# Power.net
KiCad netlist of a schematic drawn in Altium Designer
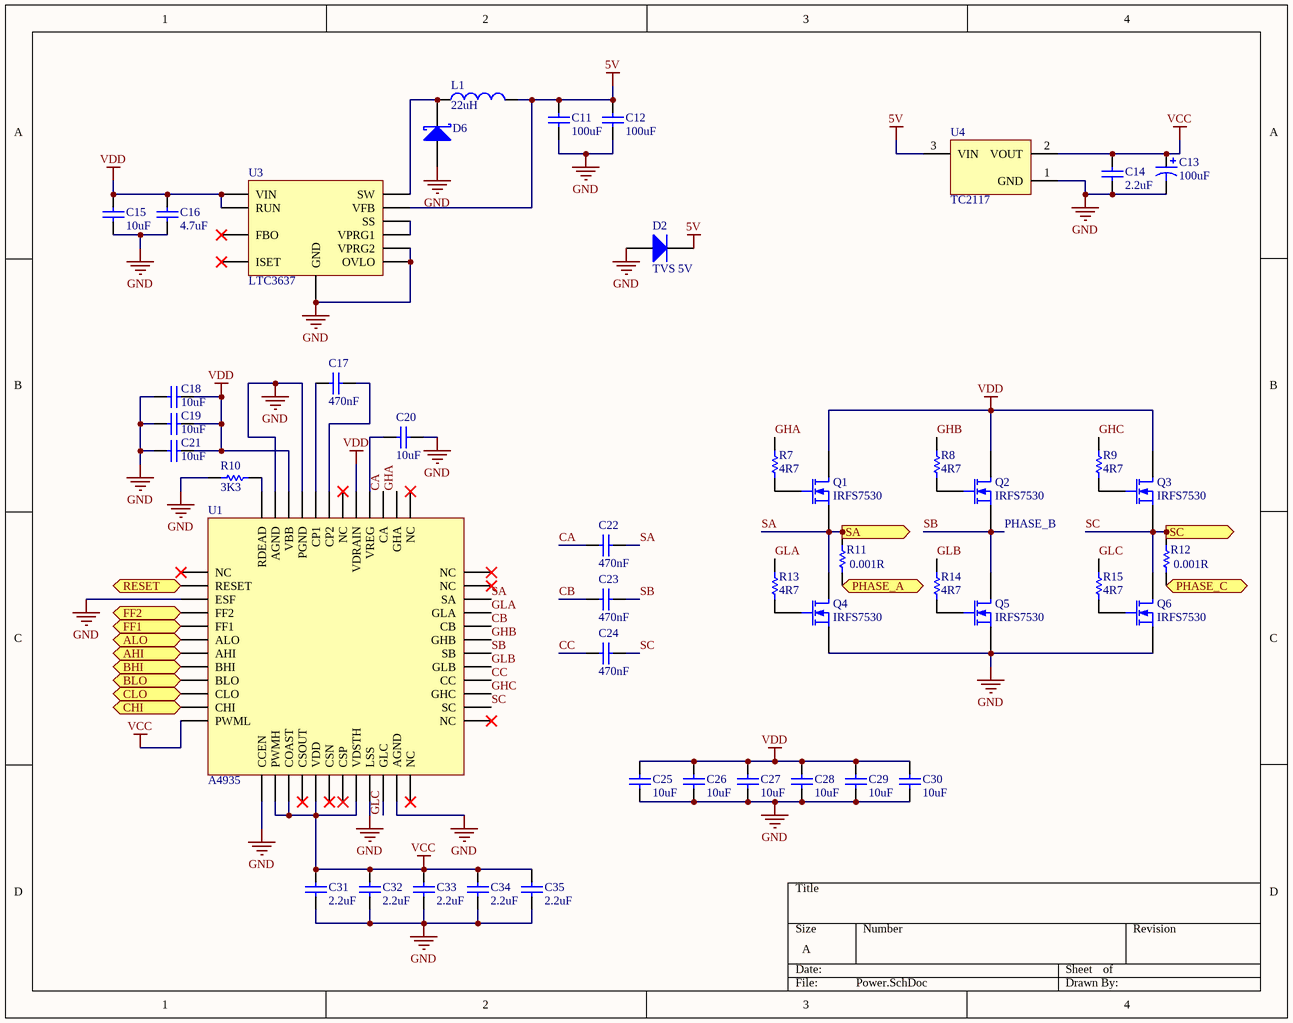
[diagram p0: Power.SchDoc]

(export (version "E")
  (design (tool "Eeschema 10.0.6"))
  (components
    (comp (ref "C11")
      (value "100uF")
      (footprint "CAPC1210(3225)280_N")
      (description "CAP 100uF 10V Â±10% 1210 (3225 Metric) Thickness 2.8mm SMD")
      (fields (field (name "TOLERANCE") "Â±10%"))
      (libsource (lib "Altium Content Vault") (part "CMP-1038-02301-1"))
    )
    (comp (ref "C12")
      (value "100uF")
      (footprint "CAPC1210(3225)280_N")
      (description "CAP 100uF 10V Â±10% 1210 (3225 Metric) Thickness 2.8mm SMD")
      (fields (field (name "TOLERANCE") "Â±10%"))
      (libsource (lib "Altium Content Vault") (part "CMP-1038-02301-1"))
    )
    (comp (ref "C13")
      (value "100uF")
      (footprint "AVX-CAPC7343_V")
      (libsource (lib "Components") (part "AVX-CAP-P-2"))
    )
    (comp (ref "C14")
      (value "2.2uF")
      (footprint "CAPC0603(1608)55_N")
      (description "CAP 2.2uF 16V Â±10% 0603 (1608 Metric) Thickness 0.55mm SMD")
      (fields (field (name "TOLERANCE") "Â±10%"))
      (libsource (lib "Altium Content Vault") (part "CMP-1035-02762-1"))
    )
    (comp (ref "C15")
      (value "10uF")
      (footprint "CAPC1206(3216)190_M")
      (description "CAP 10uF 50V Â±10% 1206 (3216 Metric) Thickness 1.9mm SMD")
      (fields (field (name "TOLERANCE") "Â±10%"))
      (libsource (lib "Altium Content Vault") (part "CAP"))
    )
    (comp (ref "C16")
      (value "4.7uF")
      (footprint "CAPC0805(2012)145_N")
      (description "CAP 4.7uF 50V Â±10% 0805 (2012 Metric) Thickness 1.45mm SMD")
      (fields (field (name "TOLERANCE") "Â±10%"))
      (libsource (lib "Altium Content Vault") (part "CAP"))
    )
    (comp (ref "C17")
      (value "470nF")
      (footprint "CAPC0603(1608)100_N")
      (description "CAP 470nF 25V Â±20% 0603 (1608 Metric) Thickness 1mm SMD")
      (fields (field (name "TOLERANCE") "Â±20%"))
      (libsource (lib "Altium Content Vault") (part "CAP"))
    )
    (comp (ref "C18")
      (value "10uF")
      (footprint "CAPC1206(3216)190_M")
      (description "CAP 10uF 50V Â±10% 1206 (3216 Metric) Thickness 1.9mm SMD")
      (fields (field (name "TOLERANCE") "Â±10%"))
      (libsource (lib "Altium Content Vault") (part "CAP"))
    )
    (comp (ref "C19")
      (value "10uF")
      (footprint "CAPC1206(3216)190_M")
      (description "CAP 10uF 50V Â±10% 1206 (3216 Metric) Thickness 1.9mm SMD")
      (fields (field (name "TOLERANCE") "Â±10%"))
      (libsource (lib "Altium Content Vault") (part "CAP"))
    )
    (comp (ref "C20")
      (value "10uF")
      (footprint "CAPC0805(2012)145_N")
      (description "CAP 10uF 25V Â±10% 0805 (2012 Metric) Thickness 1.45mm SMD")
      (fields (field (name "TOLERANCE") "Â±10%"))
      (libsource (lib "Altium Content Vault") (part "CAP"))
    )
    (comp (ref "C21")
      (value "10uF")
      (footprint "CAPC1206(3216)190_M")
      (description "CAP 10uF 50V Â±10% 1206 (3216 Metric) Thickness 1.9mm SMD")
      (fields (field (name "TOLERANCE") "Â±10%"))
      (libsource (lib "Altium Content Vault") (part "CAP"))
    )
    (comp (ref "C22")
      (value "470nF")
      (footprint "CAPC0603(1608)100_L")
      (description "CAP 470nF 25V Â±10% 0603 (1608 Metric) Thickness 1mm SMD")
      (fields (field (name "TOLERANCE") "Â±10%"))
      (libsource (lib "Altium Content Vault") (part "CAP"))
    )
    (comp (ref "C23")
      (value "470nF")
      (footprint "CAPC0603(1608)100_L")
      (description "CAP 470nF 25V Â±10% 0603 (1608 Metric) Thickness 1mm SMD")
      (fields (field (name "TOLERANCE") "Â±10%"))
      (libsource (lib "Altium Content Vault") (part "CAP"))
    )
    (comp (ref "C24")
      (value "470nF")
      (footprint "CAPC0603(1608)100_L")
      (description "CAP 470nF 25V Â±10% 0603 (1608 Metric) Thickness 1mm SMD")
      (fields (field (name "TOLERANCE") "Â±10%"))
      (libsource (lib "Altium Content Vault") (part "CAP"))
    )
    (comp (ref "C25")
      (value "10uF")
      (footprint "CAPC1206(3216)190_M")
      (description "CAP 10uF 50V Â±10% 1206 (3216 Metric) Thickness 1.9mm SMD")
      (fields (field (name "TOLERANCE") "Â±10%"))
      (libsource (lib "Altium Content Vault") (part "CMP-1037-04982-1"))
    )
    (comp (ref "C26")
      (value "10uF")
      (footprint "CAPC1206(3216)190_M")
      (description "CAP 10uF 50V Â±10% 1206 (3216 Metric) Thickness 1.9mm SMD")
      (fields (field (name "TOLERANCE") "Â±10%"))
      (libsource (lib "Altium Content Vault") (part "CAP"))
    )
    (comp (ref "C27")
      (value "10uF")
      (footprint "CAPC1206(3216)190_M")
      (description "CAP 10uF 50V Â±10% 1206 (3216 Metric) Thickness 1.9mm SMD")
      (fields (field (name "TOLERANCE") "Â±10%"))
      (libsource (lib "Altium Content Vault") (part "CAP"))
    )
    (comp (ref "C28")
      (value "10uF")
      (footprint "CAPC1206(3216)190_M")
      (description "CAP 10uF 50V Â±10% 1206 (3216 Metric) Thickness 1.9mm SMD")
      (fields (field (name "TOLERANCE") "Â±10%"))
      (libsource (lib "Altium Content Vault") (part "CMP-1037-04982-1"))
    )
    (comp (ref "C29")
      (value "10uF")
      (footprint "CAPC1206(3216)190_M")
      (description "CAP 10uF 50V Â±10% 1206 (3216 Metric) Thickness 1.9mm SMD")
      (fields (field (name "TOLERANCE") "Â±10%"))
      (libsource (lib "Altium Content Vault") (part "CAP"))
    )
    (comp (ref "C30")
      (value "10uF")
      (footprint "CAPC1206(3216)190_M")
      (description "CAP 10uF 50V Â±10% 1206 (3216 Metric) Thickness 1.9mm SMD")
      (fields (field (name "TOLERANCE") "Â±10%"))
      (libsource (lib "Altium Content Vault") (part "CAP"))
    )
    (comp (ref "C31")
      (value "2.2uF")
      (footprint "CAPC0603(1608)55_N")
      (description "CAP 2.2uF 16V Â±10% 0603 (1608 Metric) Thickness 0.55mm SMD")
      (fields (field (name "TOLERANCE") "Â±10%"))
      (libsource (lib "Altium Content Vault") (part "CMP-1035-02762-1"))
    )
    (comp (ref "C32")
      (value "2.2uF")
      (footprint "CAPC0603(1608)55_N")
      (description "CAP 2.2uF 16V Â±10% 0603 (1608 Metric) Thickness 0.55mm SMD")
      (fields (field (name "TOLERANCE") "Â±10%"))
      (libsource (lib "Altium Content Vault") (part "CMP-1035-02762-1"))
    )
    (comp (ref "C33")
      (value "2.2uF")
      (footprint "CAPC0603(1608)55_N")
      (description "CAP 2.2uF 16V Â±10% 0603 (1608 Metric) Thickness 0.55mm SMD")
      (fields (field (name "TOLERANCE") "Â±10%"))
      (libsource (lib "Altium Content Vault") (part "CMP-1035-02762-1"))
    )
    (comp (ref "C34")
      (value "2.2uF")
      (footprint "CAPC0603(1608)55_N")
      (description "CAP 2.2uF 16V Â±10% 0603 (1608 Metric) Thickness 0.55mm SMD")
      (fields (field (name "TOLERANCE") "Â±10%"))
      (libsource (lib "Altium Content Vault") (part "CMP-1035-02762-1"))
    )
    (comp (ref "C35")
      (value "2.2uF")
      (footprint "CAPC0603(1608)55_N")
      (description "CAP 2.2uF 16V Â±10% 0603 (1608 Metric) Thickness 0.55mm SMD")
      (fields (field (name "TOLERANCE") "Â±10%"))
      (libsource (lib "Altium Content Vault") (part "CMP-1035-02762-1"))
    )
    (comp (ref "D2")
      (value "TVS 5V")
      (footprint "VISH-DO-214AC-2_N")
      (fields
        (field (name "PARTNUMBER") "SMAJ5.0A-E3/61")
        (field (name "MANUFACTURER") "Vishay Semiconductor")
      )
      (libsource (lib "Altium Content Vault") (part "CMP-0548-00235-1"))
    )
    (comp (ref "D6")
      (value "~")
      (footprint "SMB")
      (description "Schottky Diode")
      (fields (field (name "PUBLISHER") "Altium Limited"))
      (libsource (lib "Miscellaneous Devices") (part "D Schottky"))
    )
    (comp (ref "L1")
      (value "22uH")
      (footprint "SDR0805-180ML")
      (description "Inductor")
      (fields (field (name "Comment") "SDR0805-180ML") (field (name "PUBLISHER") "Altium Limited"))
      (libsource (lib "Components") (part "SDR0805-180ML"))
    )
    (comp (ref "Q1")
      (value "IRFS7530")
      (footprint "DPAK127P1525X483-7N")
      (description "N-Channel MOSFET")
      (fields (field (name "PUBLISHER") "Altium Limited"))
      (libsource (lib "Components") (part "IRFS7530"))
    )
    (comp (ref "Q2")
      (value "IRFS7530")
      (footprint "DPAK127P1525X483-7N")
      (description "N-Channel MOSFET")
      (fields (field (name "PUBLISHER") "Altium Limited"))
      (libsource (lib "Components") (part "IRFS7530"))
    )
    (comp (ref "Q3")
      (value "IRFS7530")
      (footprint "DPAK127P1525X483-7N")
      (description "N-Channel MOSFET")
      (fields (field (name "PUBLISHER") "Altium Limited"))
      (libsource (lib "Components") (part "IRFS7530"))
    )
    (comp (ref "Q4")
      (value "IRFS7530")
      (footprint "DPAK127P1525X483-7N")
      (description "N-Channel MOSFET")
      (fields (field (name "PUBLISHER") "Altium Limited"))
      (libsource (lib "Components") (part "IRFS7530"))
    )
    (comp (ref "Q5")
      (value "IRFS7530")
      (footprint "DPAK127P1525X483-7N")
      (description "N-Channel MOSFET")
      (fields (field (name "PUBLISHER") "Altium Limited"))
      (libsource (lib "Components") (part "IRFS7530"))
    )
    (comp (ref "Q6")
      (value "IRFS7530")
      (footprint "DPAK127P1525X483-7N")
      (description "N-Channel MOSFET")
      (fields (field (name "PUBLISHER") "Altium Limited"))
      (libsource (lib "Components") (part "IRFS7530"))
    )
    (comp (ref "R7")
      (value "4R7")
      (footprint "RESC0603(1608)_N")
      (description "4R7 0.1W 5% 0603 (1608 Metric)  SMD")
      (fields (field (name "POWER") "0.1 W") (field (name "TOLERANCE") "5 %"))
      (libsource (lib "Altium Content Vault") (part "CMP-1012-00018-1"))
    )
    (comp (ref "R8")
      (value "4R7")
      (footprint "RESC0603(1608)_N")
      (description "4R7 0.1W 5% 0603 (1608 Metric)  SMD")
      (fields (field (name "POWER") "0.1 W") (field (name "TOLERANCE") "5 %"))
      (libsource (lib "Altium Content Vault") (part "CMP-1012-00018-1"))
    )
    (comp (ref "R9")
      (value "4R7")
      (footprint "RESC0603(1608)_N")
      (description "4R7 0.1W 5% 0603 (1608 Metric)  SMD")
      (fields (field (name "POWER") "0.1 W") (field (name "TOLERANCE") "5 %"))
      (libsource (lib "Altium Content Vault") (part "CMP-1012-00018-1"))
    )
    (comp (ref "R10")
      (value "3K3")
      (footprint "RESC0603(1608)_N")
      (description "3K3 0.1W 5% 0603 (1608 Metric)  SMD")
      (fields (field (name "TOLERANCE") "5 %") (field (name "POWER") "0.1 W"))
      (libsource (lib "Altium Content Vault") (part "CMP-1012-00086-1"))
    )
    (comp (ref "R11")
      (value "0.001R")
      (footprint "Shunt")
      (fields (field (name "PUBLISHER") "Altium Limited"))
      (libsource (lib "Components") (part "Shunt"))
    )
    (comp (ref "R12")
      (value "0.001R")
      (footprint "Shunt")
      (description "Resistor")
      (fields (field (name "PUBLISHER") "Altium Limited"))
      (libsource (lib "Components") (part "Shunt"))
    )
    (comp (ref "R13")
      (value "4R7")
      (footprint "RESC0603(1608)_N")
      (description "4R7 0.1W 5% 0603 (1608 Metric)  SMD")
      (fields (field (name "POWER") "0.1 W") (field (name "TOLERANCE") "5 %"))
      (libsource (lib "Altium Content Vault") (part "CMP-1012-00018-1"))
    )
    (comp (ref "R14")
      (value "4R7")
      (footprint "RESC0603(1608)_N")
      (description "4R7 0.1W 5% 0603 (1608 Metric)  SMD")
      (fields (field (name "POWER") "0.1 W") (field (name "TOLERANCE") "5 %"))
      (libsource (lib "Altium Content Vault") (part "CMP-1012-00018-1"))
    )
    (comp (ref "R15")
      (value "4R7")
      (footprint "RESC0603(1608)_N")
      (description "4R7 0.1W 5% 0603 (1608 Metric)  SMD")
      (fields (field (name "POWER") "0.1 W") (field (name "TOLERANCE") "5 %"))
      (libsource (lib "Altium Content Vault") (part "CMP-1012-00018-1"))
    )
    (comp (ref "U1") (value "A4935") (footprint "LQFP-48") (libsource (lib "Components") (part "A4935")))
    (comp (ref "U3")
      (value "LTC3637")
      (footprint "SON50P300X85_HS-17N")
      (libsource (lib "Components") (part "LTC3637"))
    )
    (comp (ref "U4")
      (value "TC2117")
      (footprint "SOT-223-DB3_M")
      (libsource (lib "Components") (part "PM-LINEREG-TC2117-IL4"))
    )
  )
  (nets
    (net (code "1") (name "/AHI") (class "Default")
      (node (ref "U1") (pin "7") (pinfunction "AHI_7") (pintype "passive"))
    )
    (net (code "2") (name "/ALO") (class "Default")
      (node (ref "U1") (pin "6") (pinfunction "ALO_6") (pintype "passive"))
    )
    (net (code "3") (name "/BHI") (class "Default")
      (node (ref "U1") (pin "8") (pinfunction "BHI_8") (pintype "passive"))
    )
    (net (code "4") (name "/BLO") (class "Default")
      (node (ref "U1") (pin "9") (pinfunction "BLO_9") (pintype "passive"))
    )
    (net (code "5") (name "/CA") (class "Default")
      (node (ref "C22") (pin "1") (pinfunction "1_1") (pintype "passive"))
      (node (ref "U1") (pin "39") (pinfunction "CA_39") (pintype "passive"))
    )
    (net (code "6") (name "/CB") (class "Default")
      (node (ref "C23") (pin "1") (pinfunction "1_1") (pintype "passive"))
      (node (ref "U1") (pin "32") (pinfunction "CB_32") (pintype "passive"))
    )
    (net (code "7") (name "/CC") (class "Default")
      (node (ref "C24") (pin "1") (pinfunction "1_1") (pintype "passive"))
      (node (ref "U1") (pin "28") (pinfunction "CC_28") (pintype "passive"))
    )
    (net (code "8") (name "/CHI") (class "Default")
      (node (ref "U1") (pin "11") (pinfunction "CHI_11") (pintype "passive"))
    )
    (net (code "9") (name "/CLO") (class "Default")
      (node (ref "U1") (pin "10") (pinfunction "CLO_10") (pintype "passive"))
    )
    (net (code "10") (name "/FF1") (class "Default")
      (node (ref "U1") (pin "5") (pinfunction "FF1_5") (pintype "passive"))
    )
    (net (code "11") (name "/FF2") (class "Default")
      (node (ref "U1") (pin "4") (pinfunction "FF2_4") (pintype "passive"))
    )
    (net (code "12") (name "/GHA") (class "Default")
      (node (ref "R7") (pin "2") (pinfunction "2_2") (pintype "passive"))
      (node (ref "U1") (pin "38") (pinfunction "GHA_38") (pintype "passive"))
    )
    (net (code "13") (name "/GHB") (class "Default")
      (node (ref "R8") (pin "2") (pinfunction "2_2") (pintype "passive"))
      (node (ref "U1") (pin "31") (pinfunction "GHB_31") (pintype "passive"))
    )
    (net (code "14") (name "/GHC") (class "Default")
      (node (ref "R9") (pin "2") (pinfunction "2_2") (pintype "passive"))
      (node (ref "U1") (pin "27") (pinfunction "GHC_27") (pintype "passive"))
    )
    (net (code "15") (name "/GLA") (class "Default")
      (node (ref "R13") (pin "2") (pinfunction "2_2") (pintype "passive"))
      (node (ref "U1") (pin "33") (pinfunction "GLA_33") (pintype "passive"))
    )
    (net (code "16") (name "/GLB") (class "Default")
      (node (ref "R14") (pin "2") (pinfunction "2_2") (pintype "passive"))
      (node (ref "U1") (pin "29") (pinfunction "GLB_29") (pintype "passive"))
    )
    (net (code "17") (name "/GLC") (class "Default")
      (node (ref "R15") (pin "2") (pinfunction "2_2") (pintype "passive"))
      (node (ref "U1") (pin "22") (pinfunction "GLC_22") (pintype "passive"))
    )
    (net (code "18") (name "/PHASE_A") (class "Default")
      (node (ref "R11") (pin "1") (pinfunction "1_1") (pintype "passive"))
    )
    (net (code "19") (name "/PHASE_C") (class "Default")
      (node (ref "R12") (pin "1") (pinfunction "1_1") (pintype "passive"))
    )
    (net (code "20") (name "/RESET") (class "Default")
      (node (ref "U1") (pin "2") (pinfunction "RESET_2") (pintype "passive"))
    )
    (net (code "21") (name "/SA") (class "Default")
      (node (ref "C22") (pin "2") (pinfunction "2_2") (pintype "passive"))
      (node (ref "Q1") (pin "3") (pinfunction "S_3") (pintype "passive"))
      (node (ref "Q4") (pin "1") (pinfunction "D_1") (pintype "passive"))
      (node (ref "R11") (pin "2") (pinfunction "2_2") (pintype "passive"))
      (node (ref "U1") (pin "34") (pinfunction "SA_34") (pintype "passive"))
    )
    (net (code "22") (name "/SB") (class "Default")
      (node (ref "C23") (pin "2") (pinfunction "2_2") (pintype "passive"))
      (node (ref "Q2") (pin "3") (pinfunction "S_3") (pintype "passive"))
      (node (ref "Q5") (pin "1") (pinfunction "D_1") (pintype "passive"))
      (node (ref "U1") (pin "30") (pinfunction "SB_30") (pintype "passive"))
    )
    (net (code "23") (name "/SC") (class "Default")
      (node (ref "C24") (pin "2") (pinfunction "2_2") (pintype "passive"))
      (node (ref "Q3") (pin "3") (pinfunction "S_3") (pintype "passive"))
      (node (ref "Q6") (pin "1") (pinfunction "D_1") (pintype "passive"))
      (node (ref "R12") (pin "2") (pinfunction "2_2") (pintype "passive"))
      (node (ref "U1") (pin "26") (pinfunction "SC_26") (pintype "passive"))
    )
    (net (code "24") (name "5V") (class "Default")
      (node (ref "C11") (pin "2") (pinfunction "2_2") (pintype "passive"))
      (node (ref "C12") (pin "2") (pinfunction "2_2") (pintype "passive"))
      (node (ref "D2") (pin "1") (pinfunction "K_1") (pintype "passive"))
      (node (ref "L1") (pin "2") (pinfunction "2_2") (pintype "passive"))
      (node (ref "U3") (pin "9") (pinfunction "VFB_9") (pintype "passive"))
      (node (ref "U4") (pin "3") (pinfunction "VIN_3") (pintype "power_in"))
    )
    (net (code "25") (name "GND") (class "Default")
      (node (ref "C11") (pin "1") (pinfunction "1_1") (pintype "passive"))
      (node (ref "C12") (pin "1") (pinfunction "1_1") (pintype "passive"))
      (node (ref "C13") (pin "2") (pinfunction "2_2") (pintype "passive"))
      (node (ref "C14") (pin "2") (pinfunction "2_2") (pintype "passive"))
      (node (ref "C15") (pin "1") (pinfunction "1_1") (pintype "passive"))
      (node (ref "C16") (pin "2") (pinfunction "2_2") (pintype "passive"))
      (node (ref "C18") (pin "1") (pinfunction "1_1") (pintype "passive"))
      (node (ref "C19") (pin "1") (pinfunction "1_1") (pintype "passive"))
      (node (ref "C20") (pin "2") (pinfunction "2_2") (pintype "passive"))
      (node (ref "C21") (pin "1") (pinfunction "1_1") (pintype "passive"))
      (node (ref "C25") (pin "1") (pinfunction "1_1") (pintype "passive"))
      (node (ref "C26") (pin "1") (pinfunction "1_1") (pintype "passive"))
      (node (ref "C27") (pin "1") (pinfunction "1_1") (pintype "passive"))
      (node (ref "C28") (pin "1") (pinfunction "1_1") (pintype "passive"))
      (node (ref "C29") (pin "1") (pinfunction "1_1") (pintype "passive"))
      (node (ref "C30") (pin "1") (pinfunction "1_1") (pintype "passive"))
      (node (ref "C31") (pin "1") (pinfunction "1_1") (pintype "passive"))
      (node (ref "C32") (pin "1") (pinfunction "1_1") (pintype "passive"))
      (node (ref "C33") (pin "1") (pinfunction "1_1") (pintype "passive"))
      (node (ref "C34") (pin "1") (pinfunction "1_1") (pintype "passive"))
      (node (ref "C35") (pin "1") (pinfunction "1_1") (pintype "passive"))
      (node (ref "D2") (pin "2") (pinfunction "A_2") (pintype "passive"))
      (node (ref "D6") (pin "1") (pinfunction "A_1") (pintype "passive"))
      (node (ref "Q4") (pin "3") (pinfunction "S_3") (pintype "passive"))
      (node (ref "Q5") (pin "3") (pinfunction "S_3") (pintype "passive"))
      (node (ref "Q6") (pin "3") (pinfunction "S_3") (pintype "passive"))
      (node (ref "R10") (pin "1") (pinfunction "1_1") (pintype "passive"))
      (node (ref "U1") (pin "13") (pinfunction "CCEN_13") (pintype "passive"))
      (node (ref "U1") (pin "21") (pinfunction "LSS_21") (pintype "passive"))
      (node (ref "U1") (pin "23") (pinfunction "AGND_23") (pintype "passive"))
      (node (ref "U1") (pin "3") (pinfunction "ESF_3") (pintype "passive"))
      (node (ref "U1") (pin "45") (pinfunction "PGND_45") (pintype "passive"))
      (node (ref "U1") (pin "47") (pinfunction "AGND_47") (pintype "passive"))
      (node (ref "U3") (pin "12") (pinfunction "OVLO_12") (pintype "passive"))
      (node (ref "U3") (pin "17") (pinfunction "GND_17") (pintype "passive"))
      (node (ref "U3") (pin "6") (pinfunction "VPRG2_6") (pintype "passive"))
      (node (ref "U4") (pin "1") (pinfunction "GND_1") (pintype "power_in"))
    )
    (net (code "26") (name "Net-(D6-K)") (class "Default")
      (node (ref "D6") (pin "2") (pinfunction "K_2") (pintype "passive"))
      (node (ref "L1") (pin "1") (pinfunction "1_1") (pintype "passive"))
      (node (ref "U3") (pin "1") (pinfunction "SW_1") (pintype "passive"))
    )
    (net (code "27") (name "Net-(Q1-G)") (class "Default")
      (node (ref "Q1") (pin "2") (pinfunction "G_2") (pintype "passive"))
      (node (ref "R7") (pin "1") (pinfunction "1_1") (pintype "passive"))
    )
    (net (code "28") (name "Net-(Q2-G)") (class "Default")
      (node (ref "Q2") (pin "2") (pinfunction "G_2") (pintype "passive"))
      (node (ref "R8") (pin "1") (pinfunction "1_1") (pintype "passive"))
    )
    (net (code "29") (name "Net-(Q3-G)") (class "Default")
      (node (ref "Q3") (pin "2") (pinfunction "G_2") (pintype "passive"))
      (node (ref "R9") (pin "1") (pinfunction "1_1") (pintype "passive"))
    )
    (net (code "30") (name "Net-(Q4-G)") (class "Default")
      (node (ref "Q4") (pin "2") (pinfunction "G_2") (pintype "passive"))
      (node (ref "R13") (pin "1") (pinfunction "1_1") (pintype "passive"))
    )
    (net (code "31") (name "Net-(Q5-G)") (class "Default")
      (node (ref "Q5") (pin "2") (pinfunction "G_2") (pintype "passive"))
      (node (ref "R14") (pin "1") (pinfunction "1_1") (pintype "passive"))
    )
    (net (code "32") (name "Net-(Q6-G)") (class "Default")
      (node (ref "Q6") (pin "2") (pinfunction "G_2") (pintype "passive"))
      (node (ref "R15") (pin "1") (pinfunction "1_1") (pintype "passive"))
    )
    (net (code "33") (name "Net-(U1-CP1)") (class "Default")
      (node (ref "C17") (pin "1") (pinfunction "1_1") (pintype "passive"))
      (node (ref "U1") (pin "44") (pinfunction "CP1_44") (pintype "passive"))
    )
    (net (code "34") (name "Net-(U1-CP2)") (class "Default")
      (node (ref "C17") (pin "2") (pinfunction "2_2") (pintype "passive"))
      (node (ref "U1") (pin "43") (pinfunction "CP2_43") (pintype "passive"))
    )
    (net (code "35") (name "Net-(U1-RDEAD)") (class "Default")
      (node (ref "R10") (pin "2") (pinfunction "2_2") (pintype "passive"))
      (node (ref "U1") (pin "48") (pinfunction "RDEAD_48") (pintype "passive"))
    )
    (net (code "36") (name "Net-(U1-VREG)") (class "Default")
      (node (ref "C20") (pin "1") (pinfunction "1_1") (pintype "passive"))
      (node (ref "U1") (pin "40") (pinfunction "VREG_40") (pintype "passive"))
    )
    (net (code "37") (name "Net-(U3-SS)") (class "Default")
      (node (ref "U3") (pin "10") (pinfunction "SS_10") (pintype "passive"))
      (node (ref "U3") (pin "7") (pinfunction "VPRG1_7") (pintype "passive"))
    )
    (net (code "38") (name "VCC") (class "Default")
      (node (ref "C13") (pin "1") (pinfunction "1_1") (pintype "passive"))
      (node (ref "C14") (pin "1") (pinfunction "1_1") (pintype "passive"))
      (node (ref "C31") (pin "2") (pinfunction "2_2") (pintype "passive"))
      (node (ref "C32") (pin "2") (pinfunction "2_2") (pintype "passive"))
      (node (ref "C33") (pin "2") (pinfunction "2_2") (pintype "passive"))
      (node (ref "C34") (pin "2") (pinfunction "2_2") (pintype "passive"))
      (node (ref "C35") (pin "2") (pinfunction "2_2") (pintype "passive"))
      (node (ref "U1") (pin "12") (pinfunction "PWML_12") (pintype "passive"))
      (node (ref "U1") (pin "14") (pinfunction "PWMH_14") (pintype "passive"))
      (node (ref "U1") (pin "15") (pinfunction "COAST_15") (pintype "passive"))
      (node (ref "U1") (pin "17") (pinfunction "VDD_17") (pintype "passive"))
      (node (ref "U1") (pin "20") (pinfunction "VDSTH_20") (pintype "passive"))
      (node (ref "U4") (pin "2") (pinfunction "VOUT_2") (pintype "power_in"))
    )
    (net (code "39") (name "VDD") (class "Default")
      (node (ref "C15") (pin "2") (pinfunction "2_2") (pintype "passive"))
      (node (ref "C16") (pin "1") (pinfunction "1_1") (pintype "passive"))
      (node (ref "C18") (pin "2") (pinfunction "2_2") (pintype "passive"))
      (node (ref "C19") (pin "2") (pinfunction "2_2") (pintype "passive"))
      (node (ref "C21") (pin "2") (pinfunction "2_2") (pintype "passive"))
      (node (ref "C25") (pin "2") (pinfunction "2_2") (pintype "passive"))
      (node (ref "C26") (pin "2") (pinfunction "2_2") (pintype "passive"))
      (node (ref "C27") (pin "2") (pinfunction "2_2") (pintype "passive"))
      (node (ref "C28") (pin "2") (pinfunction "2_2") (pintype "passive"))
      (node (ref "C29") (pin "2") (pinfunction "2_2") (pintype "passive"))
      (node (ref "C30") (pin "2") (pinfunction "2_2") (pintype "passive"))
      (node (ref "Q1") (pin "1") (pinfunction "D_1") (pintype "passive"))
      (node (ref "Q2") (pin "1") (pinfunction "D_1") (pintype "passive"))
      (node (ref "Q3") (pin "1") (pinfunction "D_1") (pintype "passive"))
      (node (ref "U1") (pin "41") (pinfunction "VDRAIN_41") (pintype "passive"))
      (node (ref "U1") (pin "46") (pinfunction "VBB_46") (pintype "passive"))
      (node (ref "U3") (pin "14") (pinfunction "RUN_14") (pintype "passive"))
      (node (ref "U3") (pin "3") (pinfunction "VIN_3") (pintype "passive"))
    )
    (net (code "40") (name "unconnected-(U1-CSN-Pad18)") (class "Default")
      (node (ref "U1") (pin "18") (pinfunction "CSN_18") (pintype "passive+no_connect"))
    )
    (net (code "41") (name "unconnected-(U1-CSOUT-Pad16)") (class "Default")
      (node (ref "U1") (pin "16") (pinfunction "CSOUT_16") (pintype "passive+no_connect"))
    )
    (net (code "42") (name "unconnected-(U1-CSP-Pad19)") (class "Default")
      (node (ref "U1") (pin "19") (pinfunction "CSP_19") (pintype "passive+no_connect"))
    )
    (net (code "43") (name "unconnected-(U1-NC-Pad1)") (class "Default")
      (node (ref "U1") (pin "1") (pinfunction "NC_1") (pintype "passive+no_connect"))
    )
    (net (code "44") (name "unconnected-(U1-NC-Pad24)") (class "Default")
      (node (ref "U1") (pin "24") (pinfunction "NC_24") (pintype "passive+no_connect"))
    )
    (net (code "45") (name "unconnected-(U1-NC-Pad25)") (class "Default")
      (node (ref "U1") (pin "25") (pinfunction "NC_25") (pintype "passive+no_connect"))
    )
    (net (code "46") (name "unconnected-(U1-NC-Pad35)") (class "Default")
      (node (ref "U1") (pin "35") (pinfunction "NC_35") (pintype "passive+no_connect"))
    )
    (net (code "47") (name "unconnected-(U1-NC-Pad36)") (class "Default")
      (node (ref "U1") (pin "36") (pinfunction "NC_36") (pintype "passive+no_connect"))
    )
    (net (code "48") (name "unconnected-(U1-NC-Pad37)") (class "Default")
      (node (ref "U1") (pin "37") (pinfunction "NC_37") (pintype "passive+no_connect"))
    )
    (net (code "49") (name "unconnected-(U1-NC-Pad42)") (class "Default")
      (node (ref "U1") (pin "42") (pinfunction "NC_42") (pintype "passive+no_connect"))
    )
    (net (code "50") (name "unconnected-(U3-FBO-Pad5)") (class "Default")
      (node (ref "U3") (pin "5") (pinfunction "FBO_5") (pintype "passive+no_connect"))
    )
    (net (code "51") (name "unconnected-(U3-ISET-Pad11)") (class "Default")
      (node (ref "U3") (pin "11") (pinfunction "ISET_11") (pintype "passive+no_connect"))
    )
  )
)
